# PCB.net
KiCad netlist of a schematic drawn in EasyEDA Pro
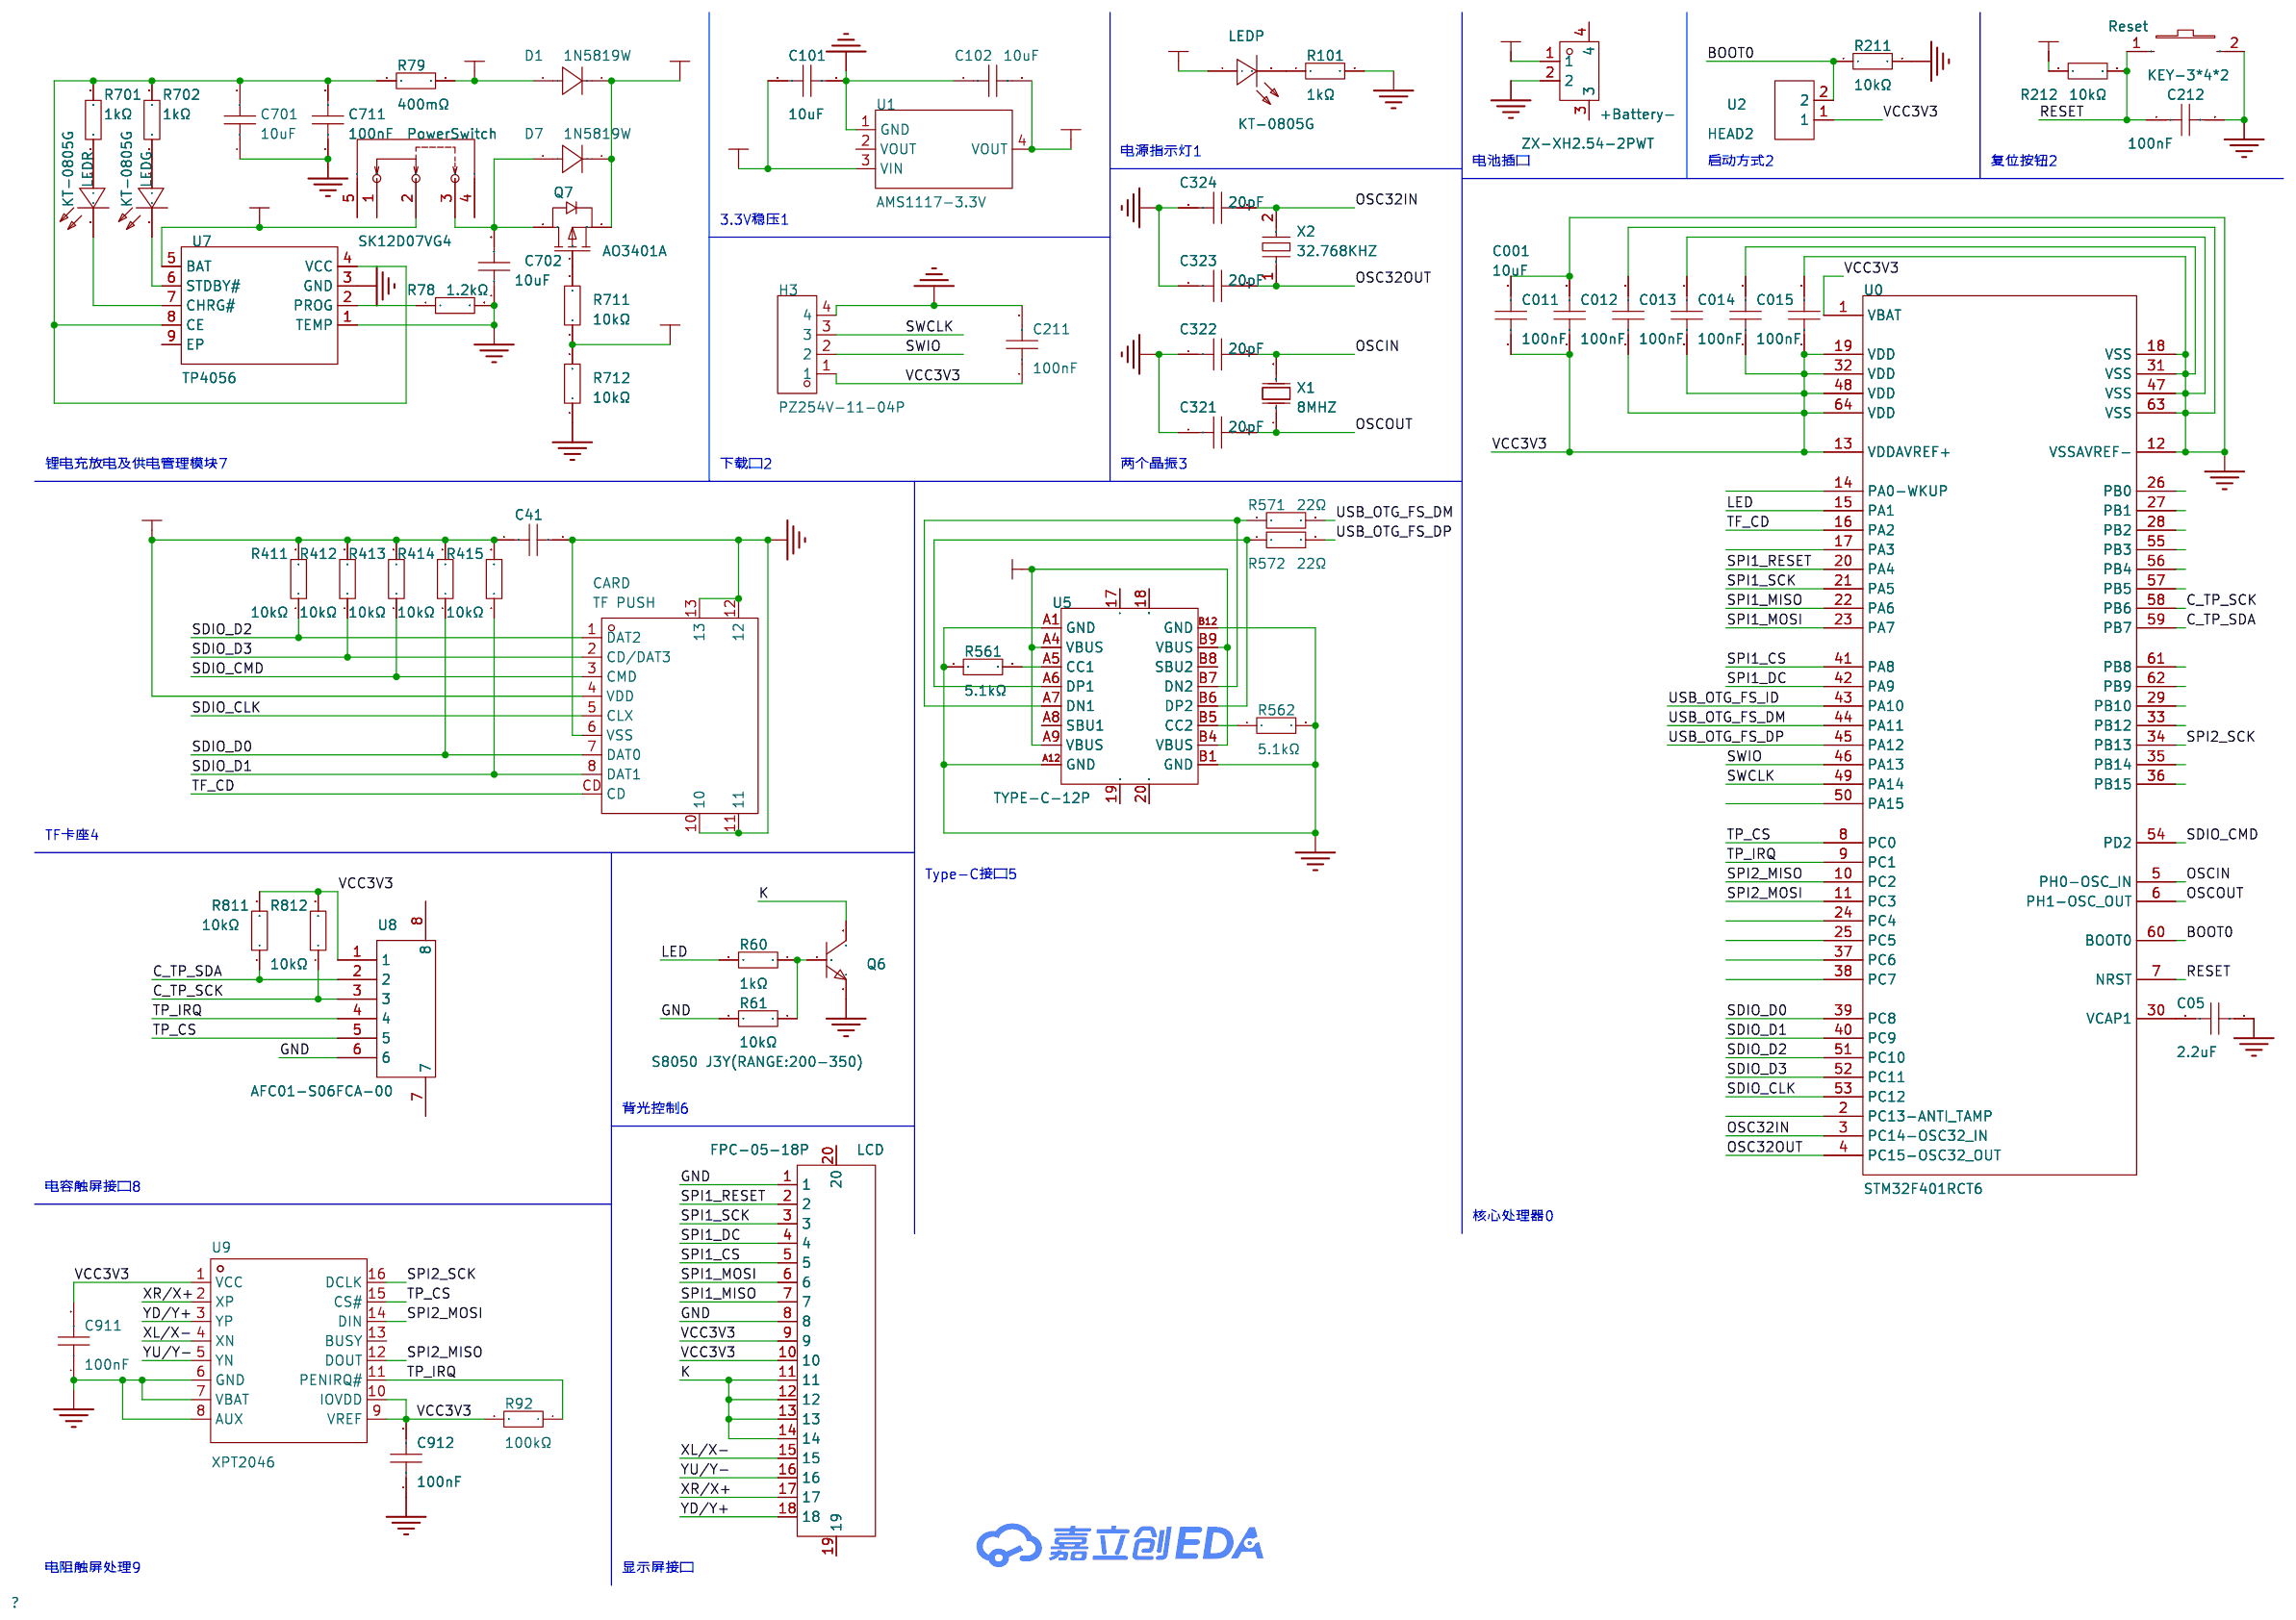
[diagram p0: schematic sheet]

(export (version "E")
  (design (tool "Eeschema 10.0.6"))
  (components
    (comp (ref "+Battery-")
      (value "ZX-XH2.54-2PWT")
      (footprint "easyedapro:CONN-SMD_2P-P2.54_MEGASTAR_ZX-XH2.54-2PWT")
      (fields (field (name "Manufacturer") "Megastar(兆星)"))
      (libsource (lib "easyedapro") (part "ZX-XH2.54-2PWT"))
    )
    (comp (ref "C001")
      (value "10uF")
      (footprint "easyedapro:C0603")
      (libsource (lib "easyedapro") (part "Capacitance"))
    )
    (comp (ref "C05")
      (value "2.2uF")
      (fields
        (field (name "Manufacturer Part") "CL10A225KO8NNNC")
        (field (name "Manufacturer") "SAMSUNG(三星)")
        (field (name "Tolerance") "±10%")
      )
      (libsource (lib "easyedapro") (part "Capacitance"))
    )
    (comp (ref "C011")
      (value "100nF")
      (footprint "easyedapro:C0603")
      (libsource (lib "easyedapro") (part "Capacitance"))
    )
    (comp (ref "C012")
      (value "100nF")
      (footprint "easyedapro:C0603")
      (libsource (lib "easyedapro") (part "Capacitance"))
    )
    (comp (ref "C013")
      (value "100nF")
      (footprint "easyedapro:C0603")
      (libsource (lib "easyedapro") (part "Capacitance"))
    )
    (comp (ref "C014")
      (value "100nF")
      (footprint "easyedapro:C0603")
      (libsource (lib "easyedapro") (part "Capacitance"))
    )
    (comp (ref "C015")
      (value "100nF")
      (footprint "easyedapro:C0603")
      (libsource (lib "easyedapro") (part "Capacitance"))
    )
    (comp (ref "C41")
      (value "100nF")
      (footprint "easyedapro:C0603")
      (fields
        (field (name "Manufacturer Part") "CGA0603X7R104K500JT")
        (field (name "Manufacturer") "HRE(芯声)")
      )
      (libsource (lib "easyedapro") (part "Capacitance"))
    )
    (comp (ref "C101")
      (value "10uF")
      (footprint "easyedapro:C0603")
      (libsource (lib "easyedapro") (part "Capacitance"))
    )
    (comp (ref "C102")
      (value "10uF")
      (footprint "easyedapro:C0603")
      (libsource (lib "easyedapro") (part "Capacitance"))
    )
    (comp (ref "C211")
      (value "100nF")
      (footprint "easyedapro:C0603")
      (libsource (lib "easyedapro") (part "Capacitance"))
    )
    (comp (ref "C212") (value "100nF") (libsource (lib "easyedapro") (part "Capacitance")))
    (comp (ref "C321") (value "20pF") (libsource (lib "easyedapro") (part "Capacitance")))
    (comp (ref "C322") (value "20pF") (libsource (lib "easyedapro") (part "Capacitance")))
    (comp (ref "C323") (value "20pF") (libsource (lib "easyedapro") (part "Capacitance")))
    (comp (ref "C324") (value "20pF") (libsource (lib "easyedapro") (part "Capacitance")))
    (comp (ref "C701")
      (value "10uF")
      (footprint "easyedapro:C0603")
      (libsource (lib "easyedapro") (part "Capacitance"))
    )
    (comp (ref "C702")
      (value "10uF")
      (footprint "easyedapro:C0603")
      (libsource (lib "easyedapro") (part "Capacitance"))
    )
    (comp (ref "C711")
      (value "100nF")
      (footprint "easyedapro:C0603")
      (libsource (lib "easyedapro") (part "Capacitance"))
    )
    (comp (ref "C911")
      (value "100nF")
      (footprint "easyedapro:C0603")
      (fields
        (field (name "Manufacturer Part") "CGA0603X7R104K500JT")
        (field (name "Manufacturer") "HRE(芯声)")
      )
      (libsource (lib "easyedapro") (part "Capacitance"))
    )
    (comp (ref "C912")
      (value "100nF")
      (footprint "easyedapro:C0603")
      (fields
        (field (name "Manufacturer Part") "CGA0603X7R104K500JT")
        (field (name "Manufacturer") "HRE(芯声)")
      )
      (libsource (lib "easyedapro") (part "Capacitance"))
    )
    (comp (ref "CARD")
      (value "TF PUSH")
      (footprint "easyedapro:TF-SMD_TF-PUSH")
      (description "卡连接方式:自弹式;卡类型:MicroSD卡(TF卡);连接器类型:卡座;本体最大高度:2mm;工作温度:-25°C~+90°C;")
      (fields (field (name "Manufacturer") "SHOU HAN(首韩)"))
      (libsource (lib "easyedapro") (part "TF PUSH"))
    )
    (comp (ref "D1")
      (value "1N5819W")
      (fields (field (name "Manufacturer") "HXY MOSFET(华轩阳电子)"))
      (libsource (lib "easyedapro") (part "1N4007_C9900004759"))
    )
    (comp (ref "D7")
      (value "1N5819W")
      (fields (field (name "Manufacturer") "HXY MOSFET(华轩阳电子)"))
      (libsource (lib "easyedapro") (part "1N4007_C9900004759"))
    )
    (comp (ref "H3")
      (value "PZ254V-11-04P")
      (footprint "easyedapro:HDR-TH_4P-P2.54-V-M")
      (fields (field (name "Manufacturer") "XFCN(兴飞)"))
      (libsource (lib "easyedapro") (part "PZ254V-11-04P"))
    )
    (comp (ref "LCD")
      (value "FPC-05-18P")
      (footprint "easyedapro:FPC-SMD_18P-P0.50_XW05200-18")
      (libsource (lib "easyedapro") (part "FPC-05-18P"))
    )
    (comp (ref "LEDG")
      (value "KT-0805G")
      (footprint "easyedapro:LED0805-R-RD")
      (fields (field (name "Manufacturer") "KENTO"))
      (libsource (lib "easyedapro") (part "0805G (Green)"))
    )
    (comp (ref "LEDP")
      (value "KT-0805G")
      (footprint "easyedapro:LED0805-R-RD")
      (fields (field (name "Manufacturer") "KENTO"))
      (libsource (lib "easyedapro") (part "0805G (Green)"))
    )
    (comp (ref "LEDR")
      (value "KT-0805G")
      (footprint "easyedapro:LED0805-R-RD")
      (fields (field (name "Manufacturer") "KENTO"))
      (libsource (lib "easyedapro") (part "0805G (Green)"))
    )
    (comp (ref "PowerSwitch")
      (value "SK12D07VG4")
      (footprint "easyedapro:SW-TH_SK12D07VG4")
      (description "电路结构:单刀双掷;安装方式:-;额定电流:500mA;额定电压:50V;工作寿命:5千次;")
      (fields (field (name "Manufacturer") "SHOU HAN(首韩)"))
      (libsource (lib "easyedapro") (part "SK12D07VG4"))
    )
    (comp (ref "Q6")
      (value "S8050 J3Y(RANGE:200-350)")
      (footprint "easyedapro:SOT-23-3_L3.0-W1.7-P0.95-LS2.9-BR")
      (description "晶体管类型:NPN;集电极电流(Ic):500mA;集射极击穿电压(Vceo):25V;耗散功率(Pd):300mW;直流电流增益(hFE):200@500mA,1V;")
      (fields (field (name "Manufacturer") "CJ(江苏长电/长晶)"))
      (libsource (lib "easyedapro") (part "S8050_C2146"))
    )
    (comp (ref "Q7")
      (value "AO3401A")
      (footprint "easyedapro:SOT-23_L2.9-W1.3-P1.90-LS2.4-BR")
      (fields (field (name "Manufacturer") "UMW(友台半导体)"))
      (libsource (lib "easyedapro") (part "AO3401A_C347476"))
    )
    (comp (ref "R60")
      (value "1kΩ")
      (footprint "easyedapro:R0603")
      (fields (field (name "Manufacturer Part") "FRC0603F1001TS") (field (name "Manufacturer") "FOJAN(富捷)"))
      (libsource (lib "easyedapro") (part "电阻"))
    )
    (comp (ref "R61")
      (value "10kΩ")
      (footprint "easyedapro:R0603")
      (fields (field (name "Manufacturer Part") "RCA0310KJLF") (field (name "Manufacturer") "HKR(香港电阻)"))
      (libsource (lib "easyedapro") (part "电阻"))
    )
    (comp (ref "R78")
      (value "1.2kΩ")
      (footprint "easyedapro:R0603")
      (libsource (lib "easyedapro") (part "电阻"))
    )
    (comp (ref "R79")
      (value "400mΩ")
      (footprint "easyedapro:R0603")
      (libsource (lib "easyedapro") (part "电阻"))
    )
    (comp (ref "R92")
      (value "100kΩ")
      (footprint "easyedapro:R0603")
      (libsource (lib "easyedapro") (part "电阻"))
    )
    (comp (ref "R101")
      (value "1kΩ")
      (footprint "easyedapro:R0603")
      (libsource (lib "easyedapro") (part "电阻"))
    )
    (comp (ref "R211")
      (value "10kΩ")
      (footprint "easyedapro:R0603")
      (fields
        (field (name "Manufacturer Part") "RCA0310KJLF")
        (field (name "Manufacturer") "HKR(香港电阻)")
        (field (name "Tolerance") "±5%")
      )
      (libsource (lib "easyedapro") (part "电阻"))
    )
    (comp (ref "R212") (value "10kΩ") (libsource (lib "easyedapro") (part "电阻")))
    (comp (ref "R411")
      (value "10kΩ")
      (footprint "easyedapro:R0603")
      (libsource (lib "easyedapro") (part "电阻"))
    )
    (comp (ref "R412")
      (value "10kΩ")
      (footprint "easyedapro:R0603")
      (libsource (lib "easyedapro") (part "电阻"))
    )
    (comp (ref "R413")
      (value "10kΩ")
      (footprint "easyedapro:R0603")
      (libsource (lib "easyedapro") (part "电阻"))
    )
    (comp (ref "R414")
      (value "10kΩ")
      (footprint "easyedapro:R0603")
      (libsource (lib "easyedapro") (part "电阻"))
    )
    (comp (ref "R415")
      (value "10kΩ")
      (footprint "easyedapro:R0603")
      (libsource (lib "easyedapro") (part "电阻"))
    )
    (comp (ref "R561")
      (value "5.1kΩ")
      (footprint "easyedapro:R0603")
      (fields
        (field (name "Manufacturer Part") "0603WAF5101T5E")
        (field (name "Manufacturer") "UNI-ROYAL(厚声)")
      )
      (libsource (lib "easyedapro") (part "电阻"))
    )
    (comp (ref "R562")
      (value "5.1kΩ")
      (footprint "easyedapro:R0603")
      (fields
        (field (name "Manufacturer Part") "0603WAF5101T5E")
        (field (name "Manufacturer") "UNI-ROYAL(厚声)")
      )
      (libsource (lib "easyedapro") (part "电阻"))
    )
    (comp (ref "R571")
      (value "22Ω")
      (footprint "easyedapro:R0603")
      (fields
        (field (name "Manufacturer Part") "0603WAF220JT5E")
        (field (name "Manufacturer") "UNI-ROYAL(厚声)")
      )
      (libsource (lib "easyedapro") (part "电阻"))
    )
    (comp (ref "R572")
      (value "22Ω")
      (footprint "easyedapro:R0603")
      (fields
        (field (name "Manufacturer Part") "0603WAF220JT5E")
        (field (name "Manufacturer") "UNI-ROYAL(厚声)")
      )
      (libsource (lib "easyedapro") (part "电阻"))
    )
    (comp (ref "R701")
      (value "1kΩ")
      (footprint "easyedapro:R0603")
      (libsource (lib "easyedapro") (part "电阻"))
    )
    (comp (ref "R702")
      (value "1kΩ")
      (footprint "easyedapro:R0603")
      (libsource (lib "easyedapro") (part "电阻"))
    )
    (comp (ref "R711")
      (value "10kΩ")
      (footprint "easyedapro:R0603")
      (libsource (lib "easyedapro") (part "电阻"))
    )
    (comp (ref "R712")
      (value "10kΩ")
      (footprint "easyedapro:R0603")
      (libsource (lib "easyedapro") (part "电阻"))
    )
    (comp (ref "R811")
      (value "10kΩ")
      (footprint "easyedapro:R0603")
      (libsource (lib "easyedapro") (part "电阻"))
    )
    (comp (ref "R812")
      (value "10kΩ")
      (footprint "easyedapro:R0603")
      (libsource (lib "easyedapro") (part "电阻"))
    )
    (comp (ref "Reset")
      (value "KEY-3*4*2")
      (footprint "easyedapro:SW-SMD_L4.0-W2.9-LS5.0")
      (libsource (lib "easyedapro") (part "KEY-3*4*2"))
    )
    (comp (ref "U0")
      (value "STM32F401RCT6")
      (footprint "easyedapro:LQFP-64_L10.0-W10.0-P0.50-LS12.0-BL")
      (description "CPU内核:ARM-M4;CPU最大主频:84MHz;应用领域:-;")
      (fields (field (name "Manufacturer") "ST(意法半导体)"))
      (libsource (lib "easyedapro") (part "STM32F401RCT6"))
    )
    (comp (ref "U1")
      (value "AMS1117-3.3V")
      (fields (field (name "Manufacturer") "JSMSEMI(杰盛微)"))
      (libsource (lib "easyedapro") (part "AMS1117-3.3"))
    )
    (comp (ref "U2")
      (value "HEAD2")
      (footprint "easyedapro:HDR-TH_2P-P2.54-V-M")
      (libsource (lib "easyedapro") (part "HEAD2"))
    )
    (comp (ref "U5")
      (value "TYPE-C-12P")
      (footprint "easyedapro:USB-SMD_TYPE-C16PIN")
      (libsource (lib "easyedapro") (part "TYPE-C-12P"))
    )
    (comp (ref "U7")
      (value "TP4056")
      (fields (field (name "Manufacturer") "GOODWORK(固得沃克)"))
      (libsource (lib "easyedapro") (part "TP4056_C725790"))
    )
    (comp (ref "U8")
      (value "AFC01-S06FCA-00")
      (footprint "easyedapro:FPC-SMD_P0.50-6P_QCHF-SM-H2.0")
      (description "间距:0.5mm;触点数量:6;锁定特性:翻盖式;安装类型:卧贴;触点类型:双侧触点/上下接;")
      (fields (field (name "Manufacturer") "JS(钜硕电子)"))
      (libsource (lib "easyedapro") (part "AFC24-S06FIC-00"))
    )
    (comp (ref "U9")
      (value "XPT2046")
      (footprint "easyedapro:TSSOP-16_L5.0-W4.4-P0.65-LS6.4-BL")
      (description "接口类型:-;")
      (fields (field (name "Manufacturer") "XPT(矽普特)"))
      (libsource (lib "easyedapro") (part "XPT2046"))
    )
    (comp (ref "X1")
      (value "8MHZ")
      (footprint "easyedapro:HC-49S_L11.5-W5.0-P4.88")
      (libsource (lib "easyedapro") (part "8MHZ_C9900021358"))
    )
    (comp (ref "X2")
      (value "32.768KHZ")
      (footprint "easyedapro:CRYSTAL-SMD_L3.2-W1.5-1")
      (libsource (lib "easyedapro") (part "32.768KHZ_C9900023773"))
    )
  )
  (nets
    (net (code "1") (name "/BOOT0") (class "Default")
      (node (ref "R211") (pin "1") (pinfunction "1_1") (pintype "input"))
      (node (ref "U0") (pin "60") (pinfunction "BOOT0_60") (pintype "unspecified"))
      (node (ref "U2") (pin "2") (pinfunction "2_2") (pintype "unspecified"))
    )
    (net (code "2") (name "/C_TP_SCK") (class "Default")
      (node (ref "R812") (pin "1") (pinfunction "1_1") (pintype "input"))
      (node (ref "U0") (pin "58") (pinfunction "PB6_58") (pintype "bidirectional"))
      (node (ref "U8") (pin "3") (pinfunction "3_3") (pintype "input"))
    )
    (net (code "3") (name "/C_TP_SDA") (class "Default")
      (node (ref "R811") (pin "1") (pinfunction "1_1") (pintype "input"))
      (node (ref "U0") (pin "59") (pinfunction "PB7_59") (pintype "bidirectional"))
      (node (ref "U8") (pin "2") (pinfunction "2_2") (pintype "input"))
    )
    (net (code "4") (name "/K") (class "Default")
      (node (ref "LCD") (pin "11") (pinfunction "11_11") (pintype "unspecified"))
      (node (ref "LCD") (pin "12") (pinfunction "12_12") (pintype "unspecified"))
      (node (ref "LCD") (pin "13") (pinfunction "13_13") (pintype "unspecified"))
      (node (ref "LCD") (pin "14") (pinfunction "14_14") (pintype "unspecified"))
      (node (ref "Q6") (pin "3") (pinfunction "C_3") (pintype "unspecified"))
    )
    (net (code "5") (name "/LED") (class "Default")
      (node (ref "R60") (pin "2") (pinfunction "2_2") (pintype "input"))
      (node (ref "U0") (pin "15") (pinfunction "PA1_15") (pintype "bidirectional"))
    )
    (net (code "6") (name "/OSC32IN") (class "Default")
      (node (ref "C324") (pin "2") (pinfunction "2_2") (pintype "input"))
      (node (ref "U0") (pin "3") (pinfunction "PC14-OSC32_IN_3") (pintype "bidirectional"))
      (node (ref "X2") (pin "2") (pinfunction "2_2") (pintype "input"))
    )
    (net (code "7") (name "/OSC32OUT") (class "Default")
      (node (ref "C323") (pin "2") (pinfunction "2_2") (pintype "input"))
      (node (ref "U0") (pin "4") (pinfunction "PC15-OSC32_OUT_4") (pintype "bidirectional"))
      (node (ref "X2") (pin "1") (pinfunction "1_1") (pintype "input"))
    )
    (net (code "8") (name "/OSCIN") (class "Default")
      (node (ref "C322") (pin "2") (pinfunction "2_2") (pintype "input"))
      (node (ref "U0") (pin "5") (pinfunction "PH0-OSC_IN_5") (pintype "bidirectional"))
      (node (ref "X1") (pin "2") (pinfunction "OSC2_2") (pintype "input"))
    )
    (net (code "9") (name "/OSCOUT") (class "Default")
      (node (ref "C321") (pin "2") (pinfunction "2_2") (pintype "input"))
      (node (ref "U0") (pin "6") (pinfunction "PH1-OSC_OUT_6") (pintype "bidirectional"))
      (node (ref "X1") (pin "1") (pinfunction "OSC1_1") (pintype "input"))
    )
    (net (code "10") (name "/RESET") (class "Default")
      (node (ref "C212") (pin "1") (pinfunction "1_1") (pintype "input"))
      (node (ref "R212") (pin "2") (pinfunction "2_2") (pintype "input"))
      (node (ref "Reset") (pin "1") (pinfunction "1_1") (pintype "input"))
      (node (ref "U0") (pin "7") (pinfunction "NRST_7") (pintype "bidirectional"))
    )
    (net (code "11") (name "/SDIO_CLK") (class "Default")
      (node (ref "CARD") (pin "5") (pinfunction "CLX_5") (pintype "unspecified"))
      (node (ref "U0") (pin "53") (pinfunction "PC12_53") (pintype "bidirectional"))
    )
    (net (code "12") (name "/SDIO_CMD") (class "Default")
      (node (ref "CARD") (pin "3") (pinfunction "CMD_3") (pintype "unspecified"))
      (node (ref "R413") (pin "1") (pinfunction "1_1") (pintype "input"))
      (node (ref "U0") (pin "54") (pinfunction "PD2_54") (pintype "bidirectional"))
    )
    (net (code "13") (name "/SDIO_D0") (class "Default")
      (node (ref "CARD") (pin "7") (pinfunction "DAT0_7") (pintype "unspecified"))
      (node (ref "R414") (pin "1") (pinfunction "1_1") (pintype "input"))
      (node (ref "U0") (pin "39") (pinfunction "PC8_39") (pintype "bidirectional"))
    )
    (net (code "14") (name "/SDIO_D1") (class "Default")
      (node (ref "CARD") (pin "8") (pinfunction "DAT1_8") (pintype "unspecified"))
      (node (ref "R415") (pin "1") (pinfunction "1_1") (pintype "input"))
      (node (ref "U0") (pin "40") (pinfunction "PC9_40") (pintype "bidirectional"))
    )
    (net (code "15") (name "/SDIO_D2") (class "Default")
      (node (ref "CARD") (pin "1") (pinfunction "DAT2_1") (pintype "unspecified"))
      (node (ref "R411") (pin "1") (pinfunction "1_1") (pintype "input"))
      (node (ref "U0") (pin "51") (pinfunction "PC10_51") (pintype "bidirectional"))
    )
    (net (code "16") (name "/SDIO_D3") (class "Default")
      (node (ref "CARD") (pin "2") (pinfunction "CD/DAT3_2") (pintype "unspecified"))
      (node (ref "R412") (pin "1") (pinfunction "1_1") (pintype "input"))
      (node (ref "U0") (pin "52") (pinfunction "PC11_52") (pintype "bidirectional"))
    )
    (net (code "17") (name "/SPI1_CS") (class "Default")
      (node (ref "LCD") (pin "5") (pinfunction "5_5") (pintype "unspecified"))
      (node (ref "U0") (pin "41") (pinfunction "PA8_41") (pintype "bidirectional"))
    )
    (net (code "18") (name "/SPI1_DC") (class "Default")
      (node (ref "LCD") (pin "4") (pinfunction "4_4") (pintype "unspecified"))
      (node (ref "U0") (pin "42") (pinfunction "PA9_42") (pintype "bidirectional"))
    )
    (net (code "19") (name "/SPI1_MISO") (class "Default")
      (node (ref "LCD") (pin "7") (pinfunction "7_7") (pintype "unspecified"))
      (node (ref "U0") (pin "22") (pinfunction "PA6_22") (pintype "bidirectional"))
    )
    (net (code "20") (name "/SPI1_MOSI") (class "Default")
      (node (ref "LCD") (pin "6") (pinfunction "6_6") (pintype "unspecified"))
      (node (ref "U0") (pin "23") (pinfunction "PA7_23") (pintype "bidirectional"))
    )
    (net (code "21") (name "/SPI1_RESET") (class "Default")
      (node (ref "LCD") (pin "2") (pinfunction "2_2") (pintype "unspecified"))
      (node (ref "U0") (pin "20") (pinfunction "PA4_20") (pintype "bidirectional"))
    )
    (net (code "22") (name "/SPI1_SCK") (class "Default")
      (node (ref "LCD") (pin "3") (pinfunction "3_3") (pintype "unspecified"))
      (node (ref "U0") (pin "21") (pinfunction "PA5_21") (pintype "bidirectional"))
    )
    (net (code "23") (name "/SPI2_MISO") (class "Default")
      (node (ref "U0") (pin "10") (pinfunction "PC2_10") (pintype "bidirectional"))
      (node (ref "U9") (pin "12") (pinfunction "DOUT_12") (pintype "unspecified"))
    )
    (net (code "24") (name "/SPI2_MOSI") (class "Default")
      (node (ref "U0") (pin "11") (pinfunction "PC3_11") (pintype "bidirectional"))
      (node (ref "U9") (pin "14") (pinfunction "DIN_14") (pintype "unspecified"))
    )
    (net (code "25") (name "/SPI2_SCK") (class "Default")
      (node (ref "U0") (pin "34") (pinfunction "PB13_34") (pintype "bidirectional"))
      (node (ref "U9") (pin "16") (pinfunction "DCLK_16") (pintype "unspecified"))
    )
    (net (code "26") (name "/SWCLK") (class "Default")
      (node (ref "H3") (pin "3") (pinfunction "3_3") (pintype "unspecified"))
      (node (ref "U0") (pin "49") (pinfunction "PA14_49") (pintype "bidirectional"))
    )
    (net (code "27") (name "/SWIO") (class "Default")
      (node (ref "H3") (pin "2") (pinfunction "2_2") (pintype "unspecified"))
      (node (ref "U0") (pin "46") (pinfunction "PA13_46") (pintype "bidirectional"))
    )
    (net (code "28") (name "/TF_CD") (class "Default")
      (node (ref "CARD") (pin "CD") (pinfunction "CD_CD") (pintype "unspecified"))
      (node (ref "U0") (pin "16") (pinfunction "PA2_16") (pintype "bidirectional"))
    )
    (net (code "29") (name "/TP_CS") (class "Default")
      (node (ref "U0") (pin "8") (pinfunction "PC0_8") (pintype "bidirectional"))
      (node (ref "U8") (pin "5") (pinfunction "5_5") (pintype "input"))
      (node (ref "U9") (pin "15") (pinfunction "CS#_15") (pintype "unspecified"))
    )
    (net (code "30") (name "/TP_IRQ") (class "Default")
      (node (ref "R92") (pin "1") (pinfunction "1_1") (pintype "input"))
      (node (ref "U0") (pin "9") (pinfunction "PC1_9") (pintype "bidirectional"))
      (node (ref "U8") (pin "4") (pinfunction "4_4") (pintype "input"))
      (node (ref "U9") (pin "11") (pinfunction "PENIRQ#_11") (pintype "unspecified"))
    )
    (net (code "31") (name "/USB_OTG_FS_DM") (class "Default")
      (node (ref "R571") (pin "2") (pinfunction "2_2") (pintype "input"))
      (node (ref "U0") (pin "44") (pinfunction "PA11_44") (pintype "bidirectional"))
    )
    (net (code "32") (name "/USB_OTG_FS_DP") (class "Default")
      (node (ref "R572") (pin "2") (pinfunction "2_2") (pintype "input"))
      (node (ref "U0") (pin "45") (pinfunction "PA12_45") (pintype "bidirectional"))
    )
    (net (code "33") (name "/USB_OTG_FS_ID") (class "Default")
      (node (ref "U0") (pin "43") (pinfunction "PA10_43") (pintype "bidirectional"))
    )
    (net (code "34") (name "/XL{slash}X-") (class "Default")
      (node (ref "LCD") (pin "15") (pinfunction "15_15") (pintype "unspecified"))
      (node (ref "U9") (pin "4") (pinfunction "XN_4") (pintype "unspecified"))
    )
    (net (code "35") (name "/XR{slash}X+") (class "Default")
      (node (ref "LCD") (pin "17") (pinfunction "17_17") (pintype "unspecified"))
      (node (ref "U9") (pin "2") (pinfunction "XP_2") (pintype "unspecified"))
    )
    (net (code "36") (name "/YD{slash}Y+") (class "Default")
      (node (ref "LCD") (pin "18") (pinfunction "18_18") (pintype "unspecified"))
      (node (ref "U9") (pin "3") (pinfunction "YP_3") (pintype "unspecified"))
    )
    (net (code "37") (name "/YU{slash}Y-") (class "Default")
      (node (ref "LCD") (pin "16") (pinfunction "16_16") (pintype "unspecified"))
      (node (ref "U9") (pin "5") (pinfunction "YN_5") (pintype "unspecified"))
    )
    (net (code "38") (name "GND") (class "Default")
      (node (ref "+Battery-") (pin "2") (pinfunction "2_2") (pintype "unspecified"))
      (node (ref "C001") (pin "2") (pinfunction "2_2") (pintype "input"))
      (node (ref "C011") (pin "2") (pinfunction "2_2") (pintype "input"))
      (node (ref "C012") (pin "2") (pinfunction "2_2") (pintype "input"))
      (node (ref "C013") (pin "1") (pinfunction "1_1") (pintype "input"))
      (node (ref "C014") (pin "2") (pinfunction "2_2") (pintype "input"))
      (node (ref "C015") (pin "2") (pinfunction "2_2") (pintype "input"))
      (node (ref "C05") (pin "1") (pinfunction "1_1") (pintype "input"))
      (node (ref "C101") (pin "2") (pinfunction "2_2") (pintype "input"))
      (node (ref "C102") (pin "1") (pinfunction "1_1") (pintype "input"))
      (node (ref "C211") (pin "2") (pinfunction "2_2") (pintype "input"))
      (node (ref "C212") (pin "2") (pinfunction "2_2") (pintype "input"))
      (node (ref "C321") (pin "1") (pinfunction "1_1") (pintype "input"))
      (node (ref "C322") (pin "1") (pinfunction "1_1") (pintype "input"))
      (node (ref "C323") (pin "1") (pinfunction "1_1") (pintype "input"))
      (node (ref "C324") (pin "1") (pinfunction "1_1") (pintype "input"))
      (node (ref "C41") (pin "2") (pinfunction "2_2") (pintype "input"))
      (node (ref "C701") (pin "1") (pinfunction "1_1") (pintype "input"))
      (node (ref "C702") (pin "1") (pinfunction "1_1") (pintype "input"))
      (node (ref "C711") (pin "1") (pinfunction "1_1") (pintype "input"))
      (node (ref "C911") (pin "1") (pinfunction "1_1") (pintype "input"))
      (node (ref "C912") (pin "1") (pinfunction "1_1") (pintype "input"))
      (node (ref "CARD") (pin "10") (pinfunction "10_10") (pintype "unspecified"))
      (node (ref "CARD") (pin "11") (pinfunction "11_11") (pintype "unspecified"))
      (node (ref "CARD") (pin "12") (pinfunction "12_12") (pintype "unspecified"))
      (node (ref "CARD") (pin "13") (pinfunction "13_13") (pintype "unspecified"))
      (node (ref "CARD") (pin "6") (pinfunction "VSS_6") (pintype "unspecified"))
      (node (ref "H3") (pin "4") (pinfunction "4_4") (pintype "unspecified"))
      (node (ref "LCD") (pin "1") (pinfunction "1_1") (pintype "unspecified"))
      (node (ref "LCD") (pin "8") (pinfunction "8_8") (pintype "unspecified"))
      (node (ref "Q6") (pin "2") (pinfunction "E_2") (pintype "unspecified"))
      (node (ref "R101") (pin "2") (pinfunction "2_2") (pintype "input"))
      (node (ref "R211") (pin "2") (pinfunction "2_2") (pintype "input"))
      (node (ref "R561") (pin "1") (pinfunction "1_1") (pintype "input"))
      (node (ref "R562") (pin "2") (pinfunction "2_2") (pintype "input"))
      (node (ref "R61") (pin "2") (pinfunction "2_2") (pintype "input"))
      (node (ref "R712") (pin "1") (pinfunction "1_1") (pintype "input"))
      (node (ref "R78") (pin "2") (pinfunction "2_2") (pintype "input"))
      (node (ref "Reset") (pin "2") (pinfunction "2_2") (pintype "input"))
      (node (ref "U0") (pin "12") (pinfunction "VSSAVREF-_12") (pintype "unspecified"))
      (node (ref "U0") (pin "18") (pinfunction "VSS_18") (pintype "unspecified"))
      (node (ref "U0") (pin "31") (pinfunction "VSS_31") (pintype "unspecified"))
      (node (ref "U0") (pin "47") (pinfunction "VSS_47") (pintype "unspecified"))
      (node (ref "U0") (pin "63") (pinfunction "VSS_63") (pintype "unspecified"))
      (node (ref "U1") (pin "1") (pinfunction "GND_1") (pintype "unspecified"))
      (node (ref "U5") (pin "A1") (pinfunction "GND_A1") (pintype "unspecified"))
      (node (ref "U5") (pin "A12") (pinfunction "GND_A12") (pintype "unspecified"))
      (node (ref "U5") (pin "B1") (pinfunction "GND_B1") (pintype "unspecified"))
      (node (ref "U5") (pin "B12") (pinfunction "GND_B12") (pintype "unspecified"))
      (node (ref "U7") (pin "1") (pinfunction "TEMP_1") (pintype "unspecified"))
      (node (ref "U7") (pin "3") (pinfunction "GND_3") (pintype "unspecified"))
      (node (ref "U8") (pin "6") (pinfunction "6_6") (pintype "input"))
      (node (ref "U9") (pin "6") (pinfunction "GND_6") (pintype "unspecified"))
      (node (ref "U9") (pin "7") (pinfunction "VBAT_7") (pintype "unspecified"))
      (node (ref "U9") (pin "8") (pinfunction "AUX_8") (pintype "unspecified"))
    )
    (net (code "39") (name "Net-(D7-A)") (class "Default")
      (node (ref "C702") (pin "2") (pinfunction "2_2") (pintype "input"))
      (node (ref "D7") (pin "2") (pinfunction "A_2") (pintype "unspecified"))
      (node (ref "PowerSwitch") (pin "3") (pinfunction "3_3") (pintype "unspecified"))
      (node (ref "Q7") (pin "3") (pinfunction "D_3") (pintype "unspecified"))
    )
    (net (code "40") (name "Net-(LEDG-A)") (class "Default")
      (node (ref "LEDG") (pin "1") (pinfunction "A_1") (pintype "unspecified"))
      (node (ref "R702") (pin "1") (pinfunction "1_1") (pintype "input"))
    )
    (net (code "41") (name "Net-(LEDG-K)") (class "Default")
      (node (ref "LEDG") (pin "2") (pinfunction "K_2") (pintype "unspecified"))
      (node (ref "U7") (pin "6") (pinfunction "STDBY#_6") (pintype "unspecified"))
    )
    (net (code "42") (name "Net-(LEDP-K)") (class "Default")
      (node (ref "LEDP") (pin "2") (pinfunction "K_2") (pintype "unspecified"))
      (node (ref "R101") (pin "1") (pinfunction "1_1") (pintype "input"))
    )
    (net (code "43") (name "Net-(LEDR-A)") (class "Default")
      (node (ref "LEDR") (pin "1") (pinfunction "A_1") (pintype "unspecified"))
      (node (ref "R701") (pin "1") (pinfunction "1_1") (pintype "input"))
    )
    (net (code "44") (name "Net-(LEDR-K)") (class "Default")
      (node (ref "LEDR") (pin "2") (pinfunction "K_2") (pintype "unspecified"))
      (node (ref "U7") (pin "7") (pinfunction "CHRG#_7") (pintype "unspecified"))
    )
    (net (code "45") (name "Net-(Q6-B)") (class "Default")
      (node (ref "Q6") (pin "1") (pinfunction "B_1") (pintype "unspecified"))
      (node (ref "R60") (pin "1") (pinfunction "1_1") (pintype "input"))
      (node (ref "R61") (pin "1") (pinfunction "1_1") (pintype "input"))
    )
    (net (code "46") (name "Net-(Q7-G)") (class "Default")
      (node (ref "Q7") (pin "1") (pinfunction "G_1") (pintype "unspecified"))
      (node (ref "R711") (pin "2") (pinfunction "2_2") (pintype "input"))
    )
    (net (code "47") (name "Net-(U0-VCAP1)") (class "Default")
      (node (ref "C05") (pin "2") (pinfunction "2_2") (pintype "input"))
      (node (ref "U0") (pin "30") (pinfunction "VCAP1_30") (pintype "unspecified"))
    )
    (net (code "48") (name "Net-(U5-CC1)") (class "Default")
      (node (ref "R561") (pin "2") (pinfunction "2_2") (pintype "input"))
      (node (ref "U5") (pin "A5") (pinfunction "CC1_A5") (pintype "unspecified"))
    )
    (net (code "49") (name "Net-(U5-CC2)") (class "Default")
      (node (ref "R562") (pin "1") (pinfunction "1_1") (pintype "input"))
      (node (ref "U5") (pin "B5") (pinfunction "CC2_B5") (pintype "unspecified"))
    )
    (net (code "50") (name "Net-(U5-DN1)") (class "Default")
      (node (ref "R571") (pin "1") (pinfunction "1_1") (pintype "input"))
      (node (ref "U5") (pin "A7") (pinfunction "DN1_A7") (pintype "unspecified"))
      (node (ref "U5") (pin "B7") (pinfunction "DN2_B7") (pintype "unspecified"))
    )
    (net (code "51") (name "Net-(U5-DP1)") (class "Default")
      (node (ref "R572") (pin "1") (pinfunction "1_1") (pintype "input"))
      (node (ref "U5") (pin "A6") (pinfunction "DP1_A6") (pintype "unspecified"))
      (node (ref "U5") (pin "B6") (pinfunction "DP2_B6") (pintype "unspecified"))
    )
    (net (code "52") (name "Net-(U7-CE)") (class "Default")
      (node (ref "C701") (pin "2") (pinfunction "2_2") (pintype "input"))
      (node (ref "C711") (pin "2") (pinfunction "2_2") (pintype "input"))
      (node (ref "R701") (pin "2") (pinfunction "2_2") (pintype "input"))
      (node (ref "R702") (pin "2") (pinfunction "2_2") (pintype "input"))
      (node (ref "R79") (pin "1") (pinfunction "1_1") (pintype "input"))
      (node (ref "U7") (pin "4") (pinfunction "VCC_4") (pintype "unspecified"))
      (node (ref "U7") (pin "8") (pinfunction "CE_8") (pintype "unspecified"))
    )
    (net (code "53") (name "Net-(U7-PROG)") (class "Default")
      (node (ref "R78") (pin "1") (pinfunction "1_1") (pintype "input"))
      (node (ref "U7") (pin "2") (pinfunction "PROG_2") (pintype "unspecified"))
    )
    (net (code "54") (name "VBAT") (class "Default")
      (node (ref "+Battery-") (pin "1") (pinfunction "1_1") (pintype "unspecified"))
      (node (ref "PowerSwitch") (pin "2") (pinfunction "2_2") (pintype "unspecified"))
      (node (ref "U7") (pin "5") (pinfunction "BAT_5") (pintype "unspecified"))
    )
    (net (code "55") (name "VBUS") (class "Default")
      (node (ref "D1") (pin "2") (pinfunction "A_2") (pintype "unspecified"))
      (node (ref "R711") (pin "1") (pinfunction "1_1") (pintype "input"))
      (node (ref "R712") (pin "2") (pinfunction "2_2") (pintype "input"))
      (node (ref "R79") (pin "2") (pinfunction "2_2") (pintype "input"))
      (node (ref "U5") (pin "A4") (pinfunction "VBUS_A4") (pintype "unspecified"))
      (node (ref "U5") (pin "A9") (pinfunction "VBUS_A9") (pintype "unspecified"))
      (node (ref "U5") (pin "B4") (pinfunction "VBUS_B4") (pintype "unspecified"))
      (node (ref "U5") (pin "B9") (pinfunction "VBUS_B9") (pintype "unspecified"))
    )
    (net (code "56") (name "VCC3V3") (class "Default")
      (node (ref "C001") (pin "1") (pinfunction "1_1") (pintype "input"))
      (node (ref "C011") (pin "1") (pinfunction "1_1") (pintype "input"))
      (node (ref "C012") (pin "1") (pinfunction "1_1") (pintype "input"))
      (node (ref "C013") (pin "2") (pinfunction "2_2") (pintype "input"))
      (node (ref "C014") (pin "1") (pinfunction "1_1") (pintype "input"))
      (node (ref "C015") (pin "1") (pinfunction "1_1") (pintype "input"))
      (node (ref "C102") (pin "2") (pinfunction "2_2") (pintype "input"))
      (node (ref "C211") (pin "1") (pinfunction "1_1") (pintype "input"))
      (node (ref "C41") (pin "1") (pinfunction "1_1") (pintype "input"))
      (node (ref "C911") (pin "2") (pinfunction "2_2") (pintype "input"))
      (node (ref "C912") (pin "2") (pinfunction "2_2") (pintype "input"))
      (node (ref "CARD") (pin "4") (pinfunction "VDD_4") (pintype "unspecified"))
      (node (ref "H3") (pin "1") (pinfunction "1_1") (pintype "unspecified"))
      (node (ref "LCD") (pin "10") (pinfunction "10_10") (pintype "unspecified"))
      (node (ref "LCD") (pin "9") (pinfunction "9_9") (pintype "unspecified"))
      (node (ref "LEDP") (pin "1") (pinfunction "A_1") (pintype "unspecified"))
      (node (ref "R212") (pin "1") (pinfunction "1_1") (pintype "input"))
      (node (ref "R411") (pin "2") (pinfunction "2_2") (pintype "input"))
      (node (ref "R412") (pin "2") (pinfunction "2_2") (pintype "input"))
      (node (ref "R413") (pin "2") (pinfunction "2_2") (pintype "input"))
      (node (ref "R414") (pin "2") (pinfunction "2_2") (pintype "input"))
      (node (ref "R415") (pin "2") (pinfunction "2_2") (pintype "input"))
      (node (ref "R811") (pin "2") (pinfunction "2_2") (pintype "input"))
      (node (ref "R812") (pin "2") (pinfunction "2_2") (pintype "input"))
      (node (ref "R92") (pin "2") (pinfunction "2_2") (pintype "input"))
      (node (ref "U0") (pin "1") (pinfunction "VBAT_1") (pintype "unspecified"))
      (node (ref "U0") (pin "13") (pinfunction "VDDAVREF+_13") (pintype "unspecified"))
      (node (ref "U0") (pin "19") (pinfunction "VDD_19") (pintype "unspecified"))
      (node (ref "U0") (pin "32") (pinfunction "VDD_32") (pintype "unspecified"))
      (node (ref "U0") (pin "48") (pinfunction "VDD_48") (pintype "unspecified"))
      (node (ref "U0") (pin "64") (pinfunction "VDD_64") (pintype "unspecified"))
      (node (ref "U1") (pin "4") (pinfunction "VOUT_4") (pintype "unspecified"))
      (node (ref "U2") (pin "1") (pinfunction "1_1") (pintype "unspecified"))
      (node (ref "U8") (pin "1") (pinfunction "1_1") (pintype "input"))
      (node (ref "U9") (pin "1") (pinfunction "VCC_1") (pintype "unspecified"))
      (node (ref "U9") (pin "10") (pinfunction "IOVDD_10") (pintype "unspecified"))
      (node (ref "U9") (pin "9") (pinfunction "VREF_9") (pintype "unspecified"))
    )
    (net (code "57") (name "VOUT") (class "Default")
      (node (ref "C101") (pin "1") (pinfunction "1_1") (pintype "input"))
      (node (ref "D1") (pin "1") (pinfunction "K_1") (pintype "unspecified"))
      (node (ref "D7") (pin "1") (pinfunction "K_1") (pintype "unspecified"))
      (node (ref "Q7") (pin "2") (pinfunction "S_2") (pintype "unspecified"))
      (node (ref "U1") (pin "3") (pinfunction "VIN_3") (pintype "unspecified"))
    )
    (net (code "58") (name "unconnected-(+Battery--Pad3)") (class "Default")
      (node (ref "+Battery-") (pin "3") (pinfunction "3_3") (pintype "unspecified"))
    )
    (net (code "59") (name "unconnected-(+Battery--Pad4)") (class "Default")
      (node (ref "+Battery-") (pin "4") (pinfunction "4_4") (pintype "unspecified"))
    )
    (net (code "60") (name "unconnected-(LCD-Pad19)") (class "Default")
      (node (ref "LCD") (pin "19") (pinfunction "19_19") (pintype "unspecified"))
    )
    (net (code "61") (name "unconnected-(LCD-Pad20)") (class "Default")
      (node (ref "LCD") (pin "20") (pinfunction "20_20") (pintype "unspecified"))
    )
    (net (code "62") (name "unconnected-(PowerSwitch-Pad1)") (class "Default")
      (node (ref "PowerSwitch") (pin "1") (pinfunction "1_1") (pintype "unspecified"))
    )
    (net (code "63") (name "unconnected-(PowerSwitch-Pad4)") (class "Default")
      (node (ref "PowerSwitch") (pin "4") (pinfunction "4_4") (pintype "unspecified"))
    )
    (net (code "64") (name "unconnected-(PowerSwitch-Pad5)") (class "Default")
      (node (ref "PowerSwitch") (pin "5") (pinfunction "5_5") (pintype "unspecified"))
    )
    (net (code "65") (name "unconnected-(U0-PA0-WKUP-Pad14)") (class "Default")
      (node (ref "U0") (pin "14") (pinfunction "PA0-WKUP_14") (pintype "bidirectional"))
    )
    (net (code "66") (name "unconnected-(U0-PA3-Pad17)") (class "Default")
      (node (ref "U0") (pin "17") (pinfunction "PA3_17") (pintype "bidirectional"))
    )
    (net (code "67") (name "unconnected-(U0-PA15-Pad50)") (class "Default")
      (node (ref "U0") (pin "50") (pinfunction "PA15_50") (pintype "bidirectional"))
    )
    (net (code "68") (name "unconnected-(U0-PB0-Pad26)") (class "Default")
      (node (ref "U0") (pin "26") (pinfunction "PB0_26") (pintype "bidirectional"))
    )
    (net (code "69") (name "unconnected-(U0-PB1-Pad27)") (class "Default")
      (node (ref "U0") (pin "27") (pinfunction "PB1_27") (pintype "bidirectional"))
    )
    (net (code "70") (name "unconnected-(U0-PB2-Pad28)") (class "Default")
      (node (ref "U0") (pin "28") (pinfunction "PB2_28") (pintype "bidirectional"))
    )
    (net (code "71") (name "unconnected-(U0-PB3-Pad55)") (class "Default")
      (node (ref "U0") (pin "55") (pinfunction "PB3_55") (pintype "bidirectional"))
    )
    (net (code "72") (name "unconnected-(U0-PB4-Pad56)") (class "Default")
      (node (ref "U0") (pin "56") (pinfunction "PB4_56") (pintype "bidirectional"))
    )
    (net (code "73") (name "unconnected-(U0-PB5-Pad57)") (class "Default")
      (node (ref "U0") (pin "57") (pinfunction "PB5_57") (pintype "bidirectional"))
    )
    (net (code "74") (name "unconnected-(U0-PB8-Pad61)") (class "Default")
      (node (ref "U0") (pin "61") (pinfunction "PB8_61") (pintype "bidirectional"))
    )
    (net (code "75") (name "unconnected-(U0-PB9-Pad62)") (class "Default")
      (node (ref "U0") (pin "62") (pinfunction "PB9_62") (pintype "bidirectional"))
    )
    (net (code "76") (name "unconnected-(U0-PB10-Pad29)") (class "Default")
      (node (ref "U0") (pin "29") (pinfunction "PB10_29") (pintype "bidirectional"))
    )
    (net (code "77") (name "unconnected-(U0-PB12-Pad33)") (class "Default")
      (node (ref "U0") (pin "33") (pinfunction "PB12_33") (pintype "bidirectional"))
    )
    (net (code "78") (name "unconnected-(U0-PB14-Pad35)") (class "Default")
      (node (ref "U0") (pin "35") (pinfunction "PB14_35") (pintype "bidirectional"))
    )
    (net (code "79") (name "unconnected-(U0-PB15-Pad36)") (class "Default")
      (node (ref "U0") (pin "36") (pinfunction "PB15_36") (pintype "bidirectional"))
    )
    (net (code "80") (name "unconnected-(U0-PC4-Pad24)") (class "Default")
      (node (ref "U0") (pin "24") (pinfunction "PC4_24") (pintype "bidirectional"))
    )
    (net (code "81") (name "unconnected-(U0-PC5-Pad25)") (class "Default")
      (node (ref "U0") (pin "25") (pinfunction "PC5_25") (pintype "bidirectional"))
    )
    (net (code "82") (name "unconnected-(U0-PC6-Pad37)") (class "Default")
      (node (ref "U0") (pin "37") (pinfunction "PC6_37") (pintype "bidirectional"))
    )
    (net (code "83") (name "unconnected-(U0-PC7-Pad38)") (class "Default")
      (node (ref "U0") (pin "38") (pinfunction "PC7_38") (pintype "bidirectional"))
    )
    (net (code "84") (name "unconnected-(U0-PC13-ANTI_TAMP-Pad2)") (class "Default")
      (node (ref "U0") (pin "2") (pinfunction "PC13-ANTI_TAMP_2") (pintype "bidirectional"))
    )
    (net (code "85") (name "unconnected-(U1-VOUT-Pad2)") (class "Default")
      (node (ref "U1") (pin "2") (pinfunction "VOUT_2") (pintype "unspecified"))
    )
    (net (code "86") (name "unconnected-(U5-Pad17)") (class "Default")
      (node (ref "U5") (pin "17") (pinfunction "17_17") (pintype "unspecified"))
    )
    (net (code "87") (name "unconnected-(U5-Pad18)") (class "Default")
      (node (ref "U5") (pin "18") (pinfunction "18_18") (pintype "unspecified"))
    )
    (net (code "88") (name "unconnected-(U5-Pad19)") (class "Default")
      (node (ref "U5") (pin "19") (pinfunction "19_19") (pintype "unspecified"))
    )
    (net (code "89") (name "unconnected-(U5-Pad20)") (class "Default")
      (node (ref "U5") (pin "20") (pinfunction "20_20") (pintype "unspecified"))
    )
    (net (code "90") (name "unconnected-(U5-SBU1-PadA8)") (class "Default")
      (node (ref "U5") (pin "A8") (pinfunction "SBU1_A8") (pintype "unspecified"))
    )
    (net (code "91") (name "unconnected-(U5-SBU2-PadB8)") (class "Default")
      (node (ref "U5") (pin "B8") (pinfunction "SBU2_B8") (pintype "unspecified"))
    )
    (net (code "92") (name "unconnected-(U7-EP-Pad9)") (class "Default")
      (node (ref "U7") (pin "9") (pinfunction "EP_9") (pintype "unspecified"))
    )
    (net (code "93") (name "unconnected-(U8-Pad7)") (class "Default")
      (node (ref "U8") (pin "7") (pinfunction "7_7") (pintype "input"))
    )
    (net (code "94") (name "unconnected-(U8-Pad8)") (class "Default")
      (node (ref "U8") (pin "8") (pinfunction "8_8") (pintype "input"))
    )
    (net (code "95") (name "unconnected-(U9-BUSY-Pad13)") (class "Default")
      (node (ref "U9") (pin "13") (pinfunction "BUSY_13") (pintype "unspecified"))
    )
  )
)
